# Inverting_TL081P.net
KiCad netlist of a schematic drawn in EAGLE
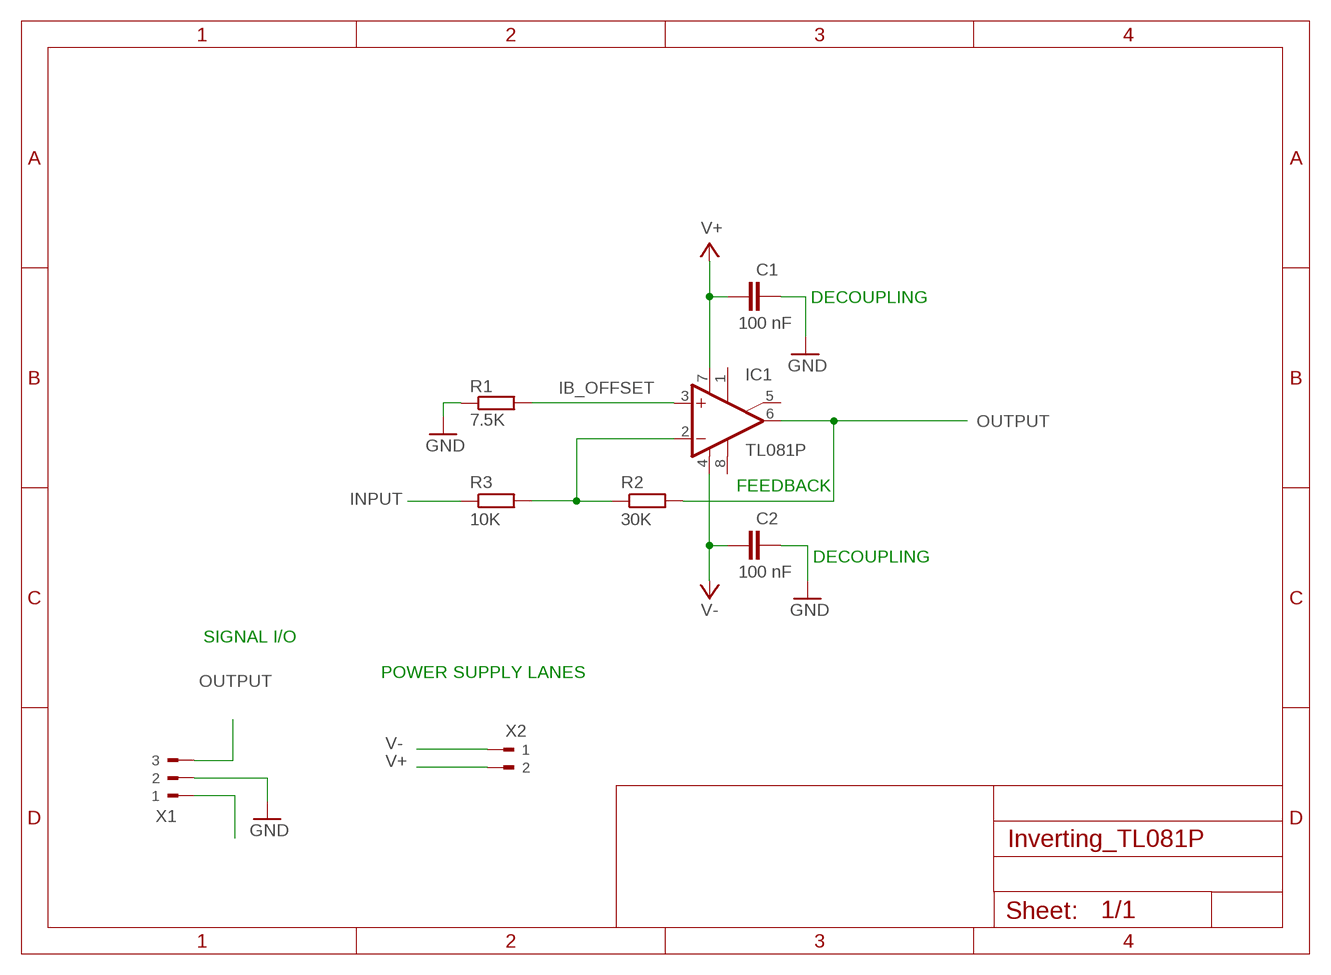
[diagram p0: schematic, sheet 1]

(export (version "E")
  (design (tool "Eeschema 10.0.6"))
  (components
    (comp (ref "C1")
      (value "100 nF")
      (footprint "eagle-import:C025-025X050")
      (libsource (lib "eagle-import") (part "C-EU025-025X050"))
    )
    (comp (ref "C2")
      (value "100 nF")
      (footprint "eagle-import:C025-025X050")
      (libsource (lib "eagle-import") (part "C-EU025-025X050"))
    )
    (comp (ref "IC1")
      (value "TL081P")
      (footprint "eagle-import:DIL08")
      (libsource (lib "eagle-import") (part "TL081P"))
    )
    (comp (ref "R1")
      (value "7.5K")
      (footprint "eagle-import:0207_10")
      (libsource (lib "eagle-import") (part "R-EU_0207/10"))
    )
    (comp (ref "R2")
      (value "30K")
      (footprint "eagle-import:0207_10")
      (libsource (lib "eagle-import") (part "R-EU_0207/10"))
    )
    (comp (ref "R3")
      (value "10K")
      (footprint "eagle-import:0207_10")
      (libsource (lib "eagle-import") (part "R-EU_0207/10"))
    )
    (comp (ref "X1")
      (value "90-3")
      (footprint "eagle-import:90-3")
      (libsource (lib "eagle-import") (part "90-3"))
    )
    (comp (ref "X2")
      (value "90-2")
      (footprint "eagle-import:90-2")
      (libsource (lib "eagle-import") (part "90-2"))
    )
  )
  (nets
    (net (code "1") (name "/IB_OFFSET") (class "Default")
      (node (ref "IC1") (pin "3") (pinfunction "+IN_3") (pintype "input"))
      (node (ref "R1") (pin "2") (pinfunction "2_2") (pintype "passive"))
    )
    (net (code "2") (name "/INPUT") (class "Default")
      (node (ref "R3") (pin "1") (pinfunction "1_1") (pintype "passive"))
      (node (ref "X1") (pin "1") (pinfunction "1_1") (pintype "passive"))
    )
    (net (code "3") (name "/OUTPUT") (class "Default")
      (node (ref "IC1") (pin "6") (pinfunction "OUT_6") (pintype "output"))
      (node (ref "R2") (pin "2") (pinfunction "2_2") (pintype "passive"))
      (node (ref "X1") (pin "3") (pinfunction "3_3") (pintype "passive"))
    )
    (net (code "4") (name "GND") (class "Default")
      (node (ref "C1") (pin "1") (pinfunction "1_1") (pintype "passive"))
      (node (ref "C2") (pin "1") (pinfunction "1_1") (pintype "passive"))
      (node (ref "R1") (pin "1") (pinfunction "1_1") (pintype "passive"))
      (node (ref "X1") (pin "2") (pinfunction "2_2") (pintype "passive"))
    )
    (net (code "5") (name "Net-(IC1--IN)") (class "Default")
      (node (ref "IC1") (pin "2") (pinfunction "-IN_2") (pintype "input"))
      (node (ref "R2") (pin "1") (pinfunction "1_1") (pintype "passive"))
      (node (ref "R3") (pin "2") (pinfunction "2_2") (pintype "passive"))
    )
    (net (code "6") (name "V+") (class "Default")
      (node (ref "C1") (pin "2") (pinfunction "2_2") (pintype "passive"))
      (node (ref "IC1") (pin "7") (pinfunction "V+_7") (pintype "power_in"))
      (node (ref "X2") (pin "2") (pinfunction "2_2") (pintype "passive"))
    )
    (net (code "7") (name "V-") (class "Default")
      (node (ref "C2") (pin "2") (pinfunction "2_2") (pintype "passive"))
      (node (ref "IC1") (pin "4") (pinfunction "V-_4") (pintype "power_in"))
      (node (ref "X2") (pin "1") (pinfunction "1_1") (pintype "passive"))
    )
    (net (code "8") (name "unconnected-(IC1-ON1-Pad1)") (class "Default")
      (node (ref "IC1") (pin "1") (pinfunction "ON1_1") (pintype "passive"))
    )
    (net (code "9") (name "unconnected-(IC1-ON2-Pad5)") (class "Default")
      (node (ref "IC1") (pin "5") (pinfunction "ON2_5") (pintype "passive"))
    )
    (net (code "10") (name "unconnected-(IC1-OPT-Pad8)") (class "Default")
      (node (ref "IC1") (pin "8") (pinfunction "OPT_8") (pintype "passive"))
    )
  )
)
